# Open-Onoff.net
KiCad netlist of a schematic drawn in EAGLE
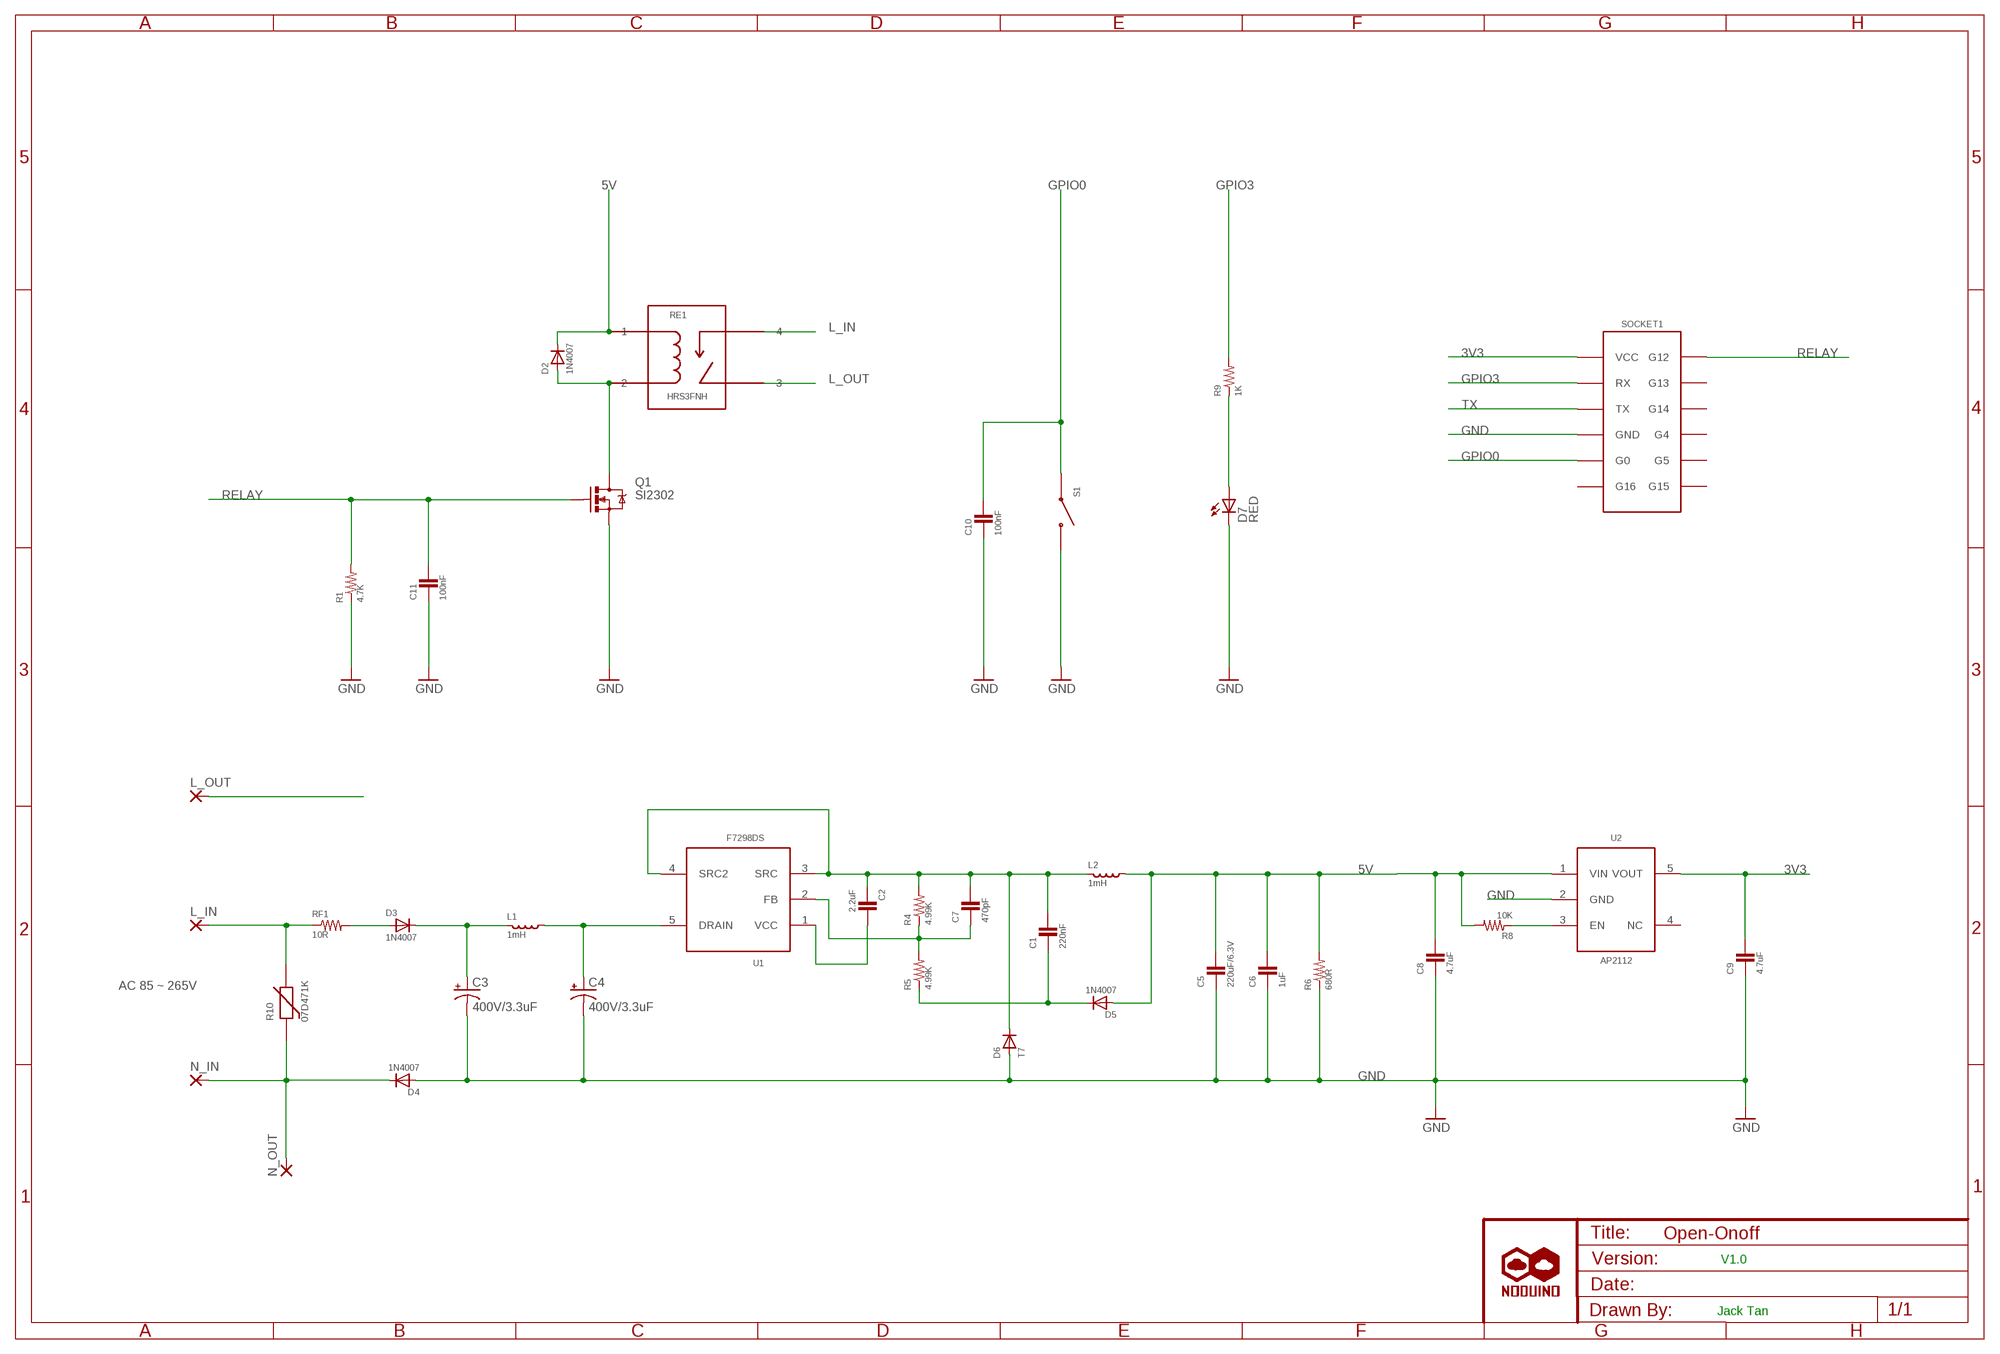
[diagram p0: schematic, sheet 1]

(export (version "E")
  (design (tool "Eeschema 10.0.6"))
  (components
    (comp (ref "C1")
      (value "220nF")
      (footprint "eagle-import:0402-CAP")
      (libsource (lib "eagle-import") (part "0402-CAP"))
    )
    (comp (ref "C2")
      (value "2.2uF")
      (footprint "eagle-import:0603-CAP")
      (libsource (lib "eagle-import") (part "0603-CAP"))
    )
    (comp (ref "C3")
      (value "400V/3.3uF")
      (footprint "eagle-import:CPOL-RADIOA-3.3UF-400V")
      (libsource (lib "eagle-import") (part "CAP_POL"))
    )
    (comp (ref "C4")
      (value "400V/3.3uF")
      (footprint "eagle-import:CPOL-RADIOA-3.3UF-400V")
      (libsource (lib "eagle-import") (part "CAP_POL"))
    )
    (comp (ref "C5")
      (value "220uF/6.3V")
      (footprint "eagle-import:B3528-CAP")
      (libsource (lib "eagle-import") (part "B3528-CAP"))
    )
    (comp (ref "C6")
      (value "1uF")
      (footprint "eagle-import:0402-CAP")
      (libsource (lib "eagle-import") (part "0402-CAP"))
    )
    (comp (ref "C7")
      (value "470pF")
      (footprint "eagle-import:0402-CAP")
      (libsource (lib "eagle-import") (part "0402-CAP"))
    )
    (comp (ref "C8")
      (value "4.7uF")
      (footprint "eagle-import:0603-CAP")
      (libsource (lib "eagle-import") (part "0603-CAP"))
    )
    (comp (ref "C9")
      (value "4.7uF")
      (footprint "eagle-import:0603-CAP")
      (libsource (lib "eagle-import") (part "0603-CAP"))
    )
    (comp (ref "C10")
      (value "100nF")
      (footprint "eagle-import:0402-CAP")
      (libsource (lib "eagle-import") (part "0402-CAP"))
    )
    (comp (ref "C11")
      (value "100nF")
      (footprint "eagle-import:0402-CAP")
      (libsource (lib "eagle-import") (part "0402-CAP"))
    )
    (comp (ref "D2")
      (value "1N4007")
      (footprint "eagle-import:SOD-323")
      (libsource (lib "eagle-import") (part "DIODESOD"))
    )
    (comp (ref "D3")
      (value "1N4007")
      (footprint "eagle-import:2.54-0.5")
      (libsource (lib "eagle-import") (part "DIODE2.54-0.5"))
    )
    (comp (ref "D4")
      (value "1N4007")
      (footprint "eagle-import:2.54-0.5")
      (libsource (lib "eagle-import") (part "DIODE2.54-0.5"))
    )
    (comp (ref "D5")
      (value "1N4007")
      (footprint "eagle-import:2.54-0.5")
      (libsource (lib "eagle-import") (part "DIODE2.54-0.5"))
    )
    (comp (ref "D6")
      (value "T7")
      (footprint "eagle-import:SOD-123")
      (libsource (lib "eagle-import") (part "SUGC10JH"))
    )
    (comp (ref "D7")
      (value "RED")
      (footprint "eagle-import:LED3MM")
      (libsource (lib "eagle-import") (part "LED3MM"))
    )
    (comp (ref "L1")
      (value "1mH")
      (footprint "eagle-import:2.54-0.5")
      (libsource (lib "eagle-import") (part "INDUCTOR2.54-0.5"))
    )
    (comp (ref "L2")
      (value "1mH")
      (footprint "eagle-import:INDUCTOR-5-0.5")
      (libsource (lib "eagle-import") (part "INDUCTOR"))
    )
    (comp (ref "L_IN")
      (value "2,15/1,0")
      (footprint "eagle-import:2,15_1,0")
      (libsource (lib "eagle-import") (part "2,15/1,0"))
    )
    (comp (ref "L_OUT")
      (value "2,15/1,0")
      (footprint "eagle-import:2,15_1,0")
      (libsource (lib "eagle-import") (part "2,15/1,0"))
    )
    (comp (ref "N_IN")
      (value "2,15/1,0")
      (footprint "eagle-import:2,15_1,0")
      (libsource (lib "eagle-import") (part "2,15/1,0"))
    )
    (comp (ref "N_OUT")
      (value "2,15/1,0")
      (footprint "eagle-import:2,15_1,0")
      (libsource (lib "eagle-import") (part "2,15/1,0"))
    )
    (comp (ref "Q1")
      (value "SI2302")
      (footprint "eagle-import:SOT23-3")
      (libsource (lib "eagle-import") (part "MOSFET-N-SMD"))
    )
    (comp (ref "R1")
      (value "4.7K")
      (footprint "eagle-import:0402-RES")
      (libsource (lib "eagle-import") (part "0402-RESISTOR"))
    )
    (comp (ref "R4")
      (value "4.99K")
      (footprint "eagle-import:0402-RES")
      (libsource (lib "eagle-import") (part "0402-RESISTOR"))
    )
    (comp (ref "R5")
      (value "4.99K")
      (footprint "eagle-import:0402-RES")
      (libsource (lib "eagle-import") (part "0402-RESISTOR"))
    )
    (comp (ref "R6")
      (value "680R")
      (footprint "eagle-import:0402-RES")
      (libsource (lib "eagle-import") (part "0402-RESISTOR"))
    )
    (comp (ref "R8")
      (value "10K")
      (footprint "eagle-import:0603-RES")
      (libsource (lib "eagle-import") (part "0603-RESISTOR"))
    )
    (comp (ref "R9")
      (value "1K")
      (footprint "eagle-import:0402-RES")
      (libsource (lib "eagle-import") (part "0402-RESISTOR"))
    )
    (comp (ref "R10")
      (value "07D471K")
      (footprint "eagle-import:07D471K")
      (libsource (lib "eagle-import") (part "07D471K"))
    )
    (comp (ref "RE1")
      (value "HRS3FNH")
      (footprint "eagle-import:HKE-HRS3FN")
      (libsource (lib "eagle-import") (part "HKE-HRS3FNH"))
    )
    (comp (ref "RF1")
      (value "10R")
      (footprint "eagle-import:2.54-0.5")
      (libsource (lib "eagle-import") (part "RESISTOR2.54-0.5"))
    )
    (comp (ref "S1")
      (value "SWITCH-4DIPTS-037")
      (footprint "eagle-import:SWITCH-TS-037")
      (libsource (lib "eagle-import") (part "SWITCH-4DIPTS-037"))
    )
    (comp (ref "SOCKET1")
      (value "MOD-SOCKET-V2.0")
      (footprint "eagle-import:MOD-PLUG-SOCKET-V2.0")
      (libsource (lib "eagle-import") (part "MOD-SOCKET-V2.0"))
    )
    (comp (ref "U$1")
      (value "NODUINO-LOGO-ALL")
      (footprint "eagle-import:NODUINO-ALL-1")
      (libsource (lib "eagle-import") (part "NODUINO-LOGO-ALL"))
    )
    (comp (ref "U1")
      (value "F7298")
      (footprint "eagle-import:SOT23-5")
      (libsource (lib "eagle-import") (part "F7298"))
    )
    (comp (ref "U2")
      (value "AP2112")
      (footprint "eagle-import:SOT23-5")
      (libsource (lib "eagle-import") (part "AP2112"))
    )
  )
  (nets
    (net (code "1") (name "/3V3") (class "Default")
      (node (ref "C9") (pin "2") (pinfunction "2_2") (pintype "passive"))
      (node (ref "SOCKET1") (pin "1") (pinfunction "VCC_1") (pintype "bidirectional"))
      (node (ref "U2") (pin "5") (pinfunction "VOUT_5") (pintype "bidirectional"))
    )
    (net (code "2") (name "/5V") (class "Default")
      (node (ref "C5") (pin "2") (pinfunction "2_2") (pintype "passive"))
      (node (ref "C6") (pin "2") (pinfunction "2_2") (pintype "passive"))
      (node (ref "C8") (pin "2") (pinfunction "2_2") (pintype "passive"))
      (node (ref "D2") (pin "1") (pinfunction "C_1") (pintype "passive"))
      (node (ref "D5") (pin "P$1") (pinfunction "A_P$1") (pintype "passive"))
      (node (ref "L2") (pin "P$2") (pinfunction "X2_P$2") (pintype "passive"))
      (node (ref "R6") (pin "2") (pinfunction "2_2") (pintype "passive"))
      (node (ref "R8") (pin "2") (pinfunction "2_2") (pintype "passive"))
      (node (ref "RE1") (pin "1") (pinfunction "1_1") (pintype "bidirectional"))
      (node (ref "U2") (pin "1") (pinfunction "VIN_1") (pintype "bidirectional"))
    )
    (net (code "3") (name "/GPIO0") (class "Default")
      (node (ref "C10") (pin "2") (pinfunction "2_2") (pintype "passive"))
      (node (ref "S1") (pin "P$3") (pinfunction "2_P$3") (pintype "bidirectional"))
      (node (ref "SOCKET1") (pin "5") (pinfunction "G0_5") (pintype "bidirectional"))
    )
    (net (code "4") (name "/GPIO3") (class "Default")
      (node (ref "R9") (pin "2") (pinfunction "2_2") (pintype "passive"))
      (node (ref "SOCKET1") (pin "2") (pinfunction "RX_2") (pintype "bidirectional"))
    )
    (net (code "5") (name "/L_IN") (class "Default")
      (node (ref "L_IN") (pin "1") (pinfunction "P_1") (pintype "passive"))
      (node (ref "R10") (pin "P$2") (pinfunction "2_P$2") (pintype "passive"))
      (node (ref "RE1") (pin "4") (pinfunction "4_4") (pintype "bidirectional"))
      (node (ref "RF1") (pin "P$1") (pinfunction "1_P$1") (pintype "passive"))
    )
    (net (code "6") (name "/L_OUT") (class "Default")
      (node (ref "L_OUT") (pin "1") (pinfunction "P_1") (pintype "passive"))
      (node (ref "RE1") (pin "3") (pinfunction "3_3") (pintype "bidirectional"))
    )
    (net (code "7") (name "/RELAY") (class "Default")
      (node (ref "C11") (pin "2") (pinfunction "2_2") (pintype "passive"))
      (node (ref "Q1") (pin "1") (pinfunction "G_1") (pintype "passive"))
      (node (ref "R1") (pin "2") (pinfunction "2_2") (pintype "passive"))
      (node (ref "SOCKET1") (pin "12") (pinfunction "G12_12") (pintype "bidirectional"))
    )
    (net (code "8") (name "/TX") (class "Default")
      (node (ref "SOCKET1") (pin "3") (pinfunction "TX_3") (pintype "bidirectional"))
    )
    (net (code "9") (name "GND") (class "Default")
      (node (ref "C10") (pin "1") (pinfunction "1_1") (pintype "passive"))
      (node (ref "C11") (pin "1") (pinfunction "1_1") (pintype "passive"))
      (node (ref "C3") (pin "P$2") (pinfunction "-_P$2") (pintype "passive"))
      (node (ref "C4") (pin "P$2") (pinfunction "-_P$2") (pintype "passive"))
      (node (ref "C5") (pin "1") (pinfunction "1_1") (pintype "passive"))
      (node (ref "C6") (pin "1") (pinfunction "1_1") (pintype "passive"))
      (node (ref "C8") (pin "1") (pinfunction "1_1") (pintype "passive"))
      (node (ref "C9") (pin "1") (pinfunction "1_1") (pintype "passive"))
      (node (ref "D4") (pin "P$1") (pinfunction "A_P$1") (pintype "passive"))
      (node (ref "D6") (pin "A") (pinfunction "A_A") (pintype "passive"))
      (node (ref "D7") (pin "K") (pinfunction "C_K") (pintype "passive"))
      (node (ref "Q1") (pin "2") (pinfunction "S_2") (pintype "passive"))
      (node (ref "R1") (pin "1") (pinfunction "1_1") (pintype "passive"))
      (node (ref "R6") (pin "1") (pinfunction "1_1") (pintype "passive"))
      (node (ref "S1") (pin "P$1") (pinfunction "1_P$1") (pintype "bidirectional"))
      (node (ref "SOCKET1") (pin "4") (pinfunction "GND_4") (pintype "bidirectional"))
      (node (ref "U2") (pin "2") (pinfunction "GND_2") (pintype "bidirectional"))
    )
    (net (code "10") (name "Net-(C3-+)") (class "Default")
      (node (ref "C3") (pin "P$1") (pinfunction "+_P$1") (pintype "passive"))
      (node (ref "D3") (pin "P$2") (pinfunction "C_P$2") (pintype "passive"))
      (node (ref "L1") (pin "P$1") (pinfunction "X1_P$1") (pintype "passive"))
    )
    (net (code "11") (name "Net-(C4-+)") (class "Default")
      (node (ref "C4") (pin "P$1") (pinfunction "+_P$1") (pintype "passive"))
      (node (ref "L1") (pin "P$2") (pinfunction "X2_P$2") (pintype "passive"))
      (node (ref "U1") (pin "5") (pinfunction "DRAIN_5") (pintype "bidirectional"))
    )
    (net (code "12") (name "Net-(D2-A)") (class "Default")
      (node (ref "D2") (pin "2") (pinfunction "A_2") (pintype "passive"))
      (node (ref "Q1") (pin "3") (pinfunction "D_3") (pintype "passive"))
      (node (ref "RE1") (pin "2") (pinfunction "2_2") (pintype "bidirectional"))
    )
    (net (code "13") (name "Net-(D3-A)") (class "Default")
      (node (ref "D3") (pin "P$1") (pinfunction "A_P$1") (pintype "passive"))
      (node (ref "RF1") (pin "P$2") (pinfunction "2_P$2") (pintype "passive"))
    )
    (net (code "14") (name "Net-(D4-C)") (class "Default")
      (node (ref "D4") (pin "P$2") (pinfunction "C_P$2") (pintype "passive"))
      (node (ref "N_IN") (pin "1") (pinfunction "P_1") (pintype "passive"))
      (node (ref "N_OUT") (pin "1") (pinfunction "P_1") (pintype "passive"))
      (node (ref "R10") (pin "P$1") (pinfunction "1_P$1") (pintype "passive"))
    )
    (net (code "15") (name "Net-(D5-C)") (class "Default")
      (node (ref "C1") (pin "1") (pinfunction "1_1") (pintype "passive"))
      (node (ref "D5") (pin "P$2") (pinfunction "C_P$2") (pintype "passive"))
      (node (ref "R5") (pin "1") (pinfunction "1_1") (pintype "passive"))
    )
    (net (code "16") (name "Net-(D7-PadA)") (class "Default")
      (node (ref "D7") (pin "A") (pinfunction "A_A") (pintype "passive"))
      (node (ref "R9") (pin "1") (pinfunction "1_1") (pintype "passive"))
    )
    (net (code "17") (name "Net-(L2-X1)") (class "Default")
      (node (ref "C1") (pin "2") (pinfunction "2_2") (pintype "passive"))
      (node (ref "C2") (pin "1") (pinfunction "1_1") (pintype "passive"))
      (node (ref "C7") (pin "2") (pinfunction "2_2") (pintype "passive"))
      (node (ref "D6") (pin "C") (pinfunction "C_C") (pintype "passive"))
      (node (ref "L2") (pin "P$1") (pinfunction "X1_P$1") (pintype "passive"))
      (node (ref "R4") (pin "2") (pinfunction "2_2") (pintype "passive"))
      (node (ref "U1") (pin "3") (pinfunction "SRC_3") (pintype "bidirectional"))
      (node (ref "U1") (pin "4") (pinfunction "SRC2_4") (pintype "bidirectional"))
    )
    (net (code "18") (name "Net-(U1-FB)") (class "Default")
      (node (ref "C7") (pin "1") (pinfunction "1_1") (pintype "passive"))
      (node (ref "R4") (pin "1") (pinfunction "1_1") (pintype "passive"))
      (node (ref "R5") (pin "2") (pinfunction "2_2") (pintype "passive"))
      (node (ref "U1") (pin "2") (pinfunction "FB_2") (pintype "bidirectional"))
    )
    (net (code "19") (name "Net-(U1-VCC)") (class "Default")
      (node (ref "C2") (pin "2") (pinfunction "2_2") (pintype "passive"))
      (node (ref "U1") (pin "1") (pinfunction "VCC_1") (pintype "bidirectional"))
    )
    (net (code "20") (name "Net-(U2-EN)") (class "Default")
      (node (ref "R8") (pin "1") (pinfunction "1_1") (pintype "passive"))
      (node (ref "U2") (pin "3") (pinfunction "EN_3") (pintype "bidirectional"))
    )
    (net (code "21") (name "unconnected-(SOCKET1-G4-Pad9)") (class "Default")
      (node (ref "SOCKET1") (pin "9") (pinfunction "G4_9") (pintype "bidirectional"))
    )
    (net (code "22") (name "unconnected-(SOCKET1-G5-Pad8)") (class "Default")
      (node (ref "SOCKET1") (pin "8") (pinfunction "G5_8") (pintype "bidirectional"))
    )
    (net (code "23") (name "unconnected-(SOCKET1-G13-Pad11)") (class "Default")
      (node (ref "SOCKET1") (pin "11") (pinfunction "G13_11") (pintype "bidirectional"))
    )
    (net (code "24") (name "unconnected-(SOCKET1-G14-Pad10)") (class "Default")
      (node (ref "SOCKET1") (pin "10") (pinfunction "G14_10") (pintype "bidirectional"))
    )
    (net (code "25") (name "unconnected-(SOCKET1-G15-Pad7)") (class "Default")
      (node (ref "SOCKET1") (pin "7") (pinfunction "G15_7") (pintype "bidirectional"))
    )
    (net (code "26") (name "unconnected-(SOCKET1-G16-Pad6)") (class "Default")
      (node (ref "SOCKET1") (pin "6") (pinfunction "G16_6") (pintype "bidirectional"))
    )
    (net (code "27") (name "unconnected-(U2-NC-Pad4)") (class "Default")
      (node (ref "U2") (pin "4") (pinfunction "NC_4") (pintype "bidirectional"))
    )
  )
)
